# working.net
KiCad netlist of a schematic drawn in EAGLE
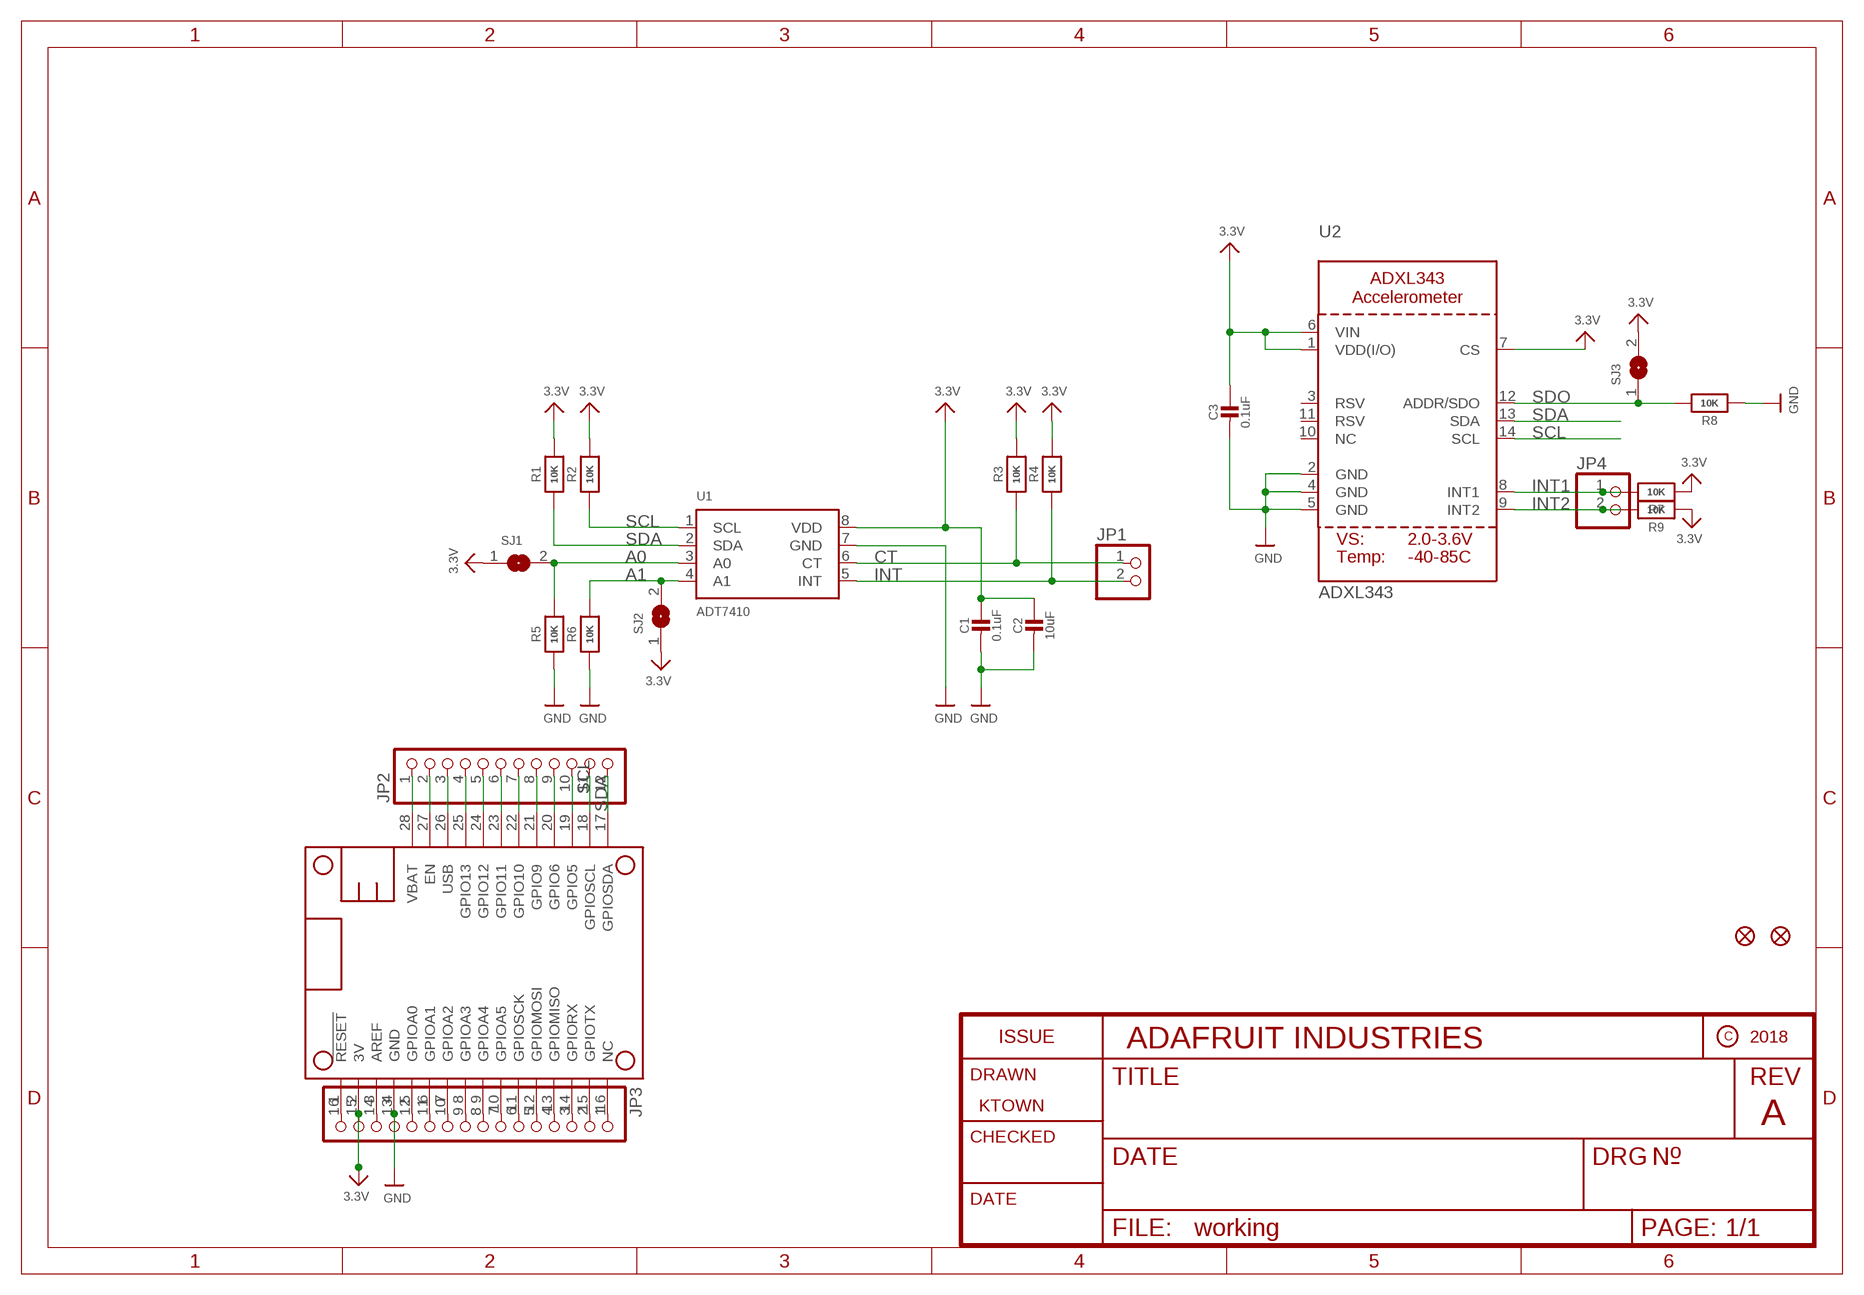
[diagram p0: schematic, sheet 1]

(export (version "E")
  (design (tool "Eeschema 10.0.6"))
  (components
    (comp (ref "C1")
      (value "0.1uF")
      (footprint "eagle-import:0603-NO")
      (libsource (lib "eagle-import") (part "CAP_CERAMIC0603_NO"))
    )
    (comp (ref "C2")
      (value "10uF")
      (footprint "eagle-import:0805-NO")
      (libsource (lib "eagle-import") (part "CAP_CERAMIC0805-NOOUTLINE"))
    )
    (comp (ref "C3")
      (value "0.1uF")
      (footprint "eagle-import:0603-NO")
      (libsource (lib "eagle-import") (part "CAP_CERAMIC0603_NO"))
    )
    (comp (ref "FID1")
      (value "FIDUCIAL_1MM")
      (footprint "eagle-import:FIDUCIAL_1MM")
      (libsource (lib "eagle-import") (part "FIDUCIAL_1MM"))
    )
    (comp (ref "FID2")
      (value "FIDUCIAL_1MM")
      (footprint "eagle-import:FIDUCIAL_1MM")
      (libsource (lib "eagle-import") (part "FIDUCIAL_1MM"))
    )
    (comp (ref "JP1")
      (value "HEADER-1X2ROUND")
      (footprint "eagle-import:1X02_ROUND")
      (libsource (lib "eagle-import") (part "HEADER-1X2ROUND"))
    )
    (comp (ref "JP2")
      (value "HEADER-1X1276MIL")
      (footprint "eagle-import:1X12_ROUND_76MIL")
      (libsource (lib "eagle-import") (part "HEADER-1X1276MIL"))
    )
    (comp (ref "JP3")
      (value "HEADER-1X16_76MIL")
      (footprint "eagle-import:1X16_ROUND_76MIL")
      (libsource (lib "eagle-import") (part "HEADER-1X16_76MIL"))
    )
    (comp (ref "JP4")
      (value "HEADER-1X2ROUND")
      (footprint "eagle-import:1X02_ROUND")
      (libsource (lib "eagle-import") (part "HEADER-1X2ROUND"))
    )
    (comp (ref "MS1")
      (value "FEATHERWING")
      (footprint "eagle-import:FEATHERWING")
      (libsource (lib "eagle-import") (part "FEATHERWING"))
    )
    (comp (ref "R1")
      (value "10K")
      (footprint "eagle-import:0603-NO")
      (libsource (lib "eagle-import") (part "RESISTOR_0603_NOOUT"))
    )
    (comp (ref "R2")
      (value "10K")
      (footprint "eagle-import:0603-NO")
      (libsource (lib "eagle-import") (part "RESISTOR_0603_NOOUT"))
    )
    (comp (ref "R3")
      (value "10K")
      (footprint "eagle-import:0603-NO")
      (libsource (lib "eagle-import") (part "RESISTOR_0603_NOOUT"))
    )
    (comp (ref "R4")
      (value "10K")
      (footprint "eagle-import:0603-NO")
      (libsource (lib "eagle-import") (part "RESISTOR_0603_NOOUT"))
    )
    (comp (ref "R5")
      (value "10K")
      (footprint "eagle-import:0603-NO")
      (libsource (lib "eagle-import") (part "RESISTOR_0603_NOOUT"))
    )
    (comp (ref "R6")
      (value "10K")
      (footprint "eagle-import:0603-NO")
      (libsource (lib "eagle-import") (part "RESISTOR_0603_NOOUT"))
    )
    (comp (ref "R7")
      (value "10K")
      (footprint "eagle-import:0603-NO")
      (libsource (lib "eagle-import") (part "RESISTOR_0603_NOOUT"))
    )
    (comp (ref "R8")
      (value "10K")
      (footprint "eagle-import:0603-NO")
      (libsource (lib "eagle-import") (part "RESISTOR_0603_NOOUT"))
    )
    (comp (ref "R9")
      (value "10K")
      (footprint "eagle-import:0603-NO")
      (libsource (lib "eagle-import") (part "RESISTOR_0603_NOOUT"))
    )
    (comp (ref "SJ1")
      (value "SOLDERJUMPER")
      (footprint "eagle-import:SOLDERJUMPER_ARROW_NOPASTE")
      (libsource (lib "eagle-import") (part "SOLDERJUMPER"))
    )
    (comp (ref "SJ2")
      (value "SOLDERJUMPER")
      (footprint "eagle-import:SOLDERJUMPER_ARROW_NOPASTE")
      (libsource (lib "eagle-import") (part "SOLDERJUMPER"))
    )
    (comp (ref "SJ3")
      (value "SOLDERJUMPER")
      (footprint "eagle-import:SOLDERJUMPER_ARROW_NOPASTE")
      (libsource (lib "eagle-import") (part "SOLDERJUMPER"))
    )
    (comp (ref "U1")
      (value "ADT7410")
      (footprint "eagle-import:SOIC8_150MIL")
      (libsource (lib "eagle-import") (part "TEMP_ADT7410"))
    )
    (comp (ref "U2")
      (value "ADXL343")
      (footprint "eagle-import:LGA14")
      (libsource (lib "eagle-import") (part "ACCEL_ADXL343"))
    )
  )
  (nets
    (net (code "1") (name "/A0") (class "Default")
      (node (ref "R5") (pin "2") (pinfunction "2_2") (pintype "passive"))
      (node (ref "SJ1") (pin "2") (pinfunction "2_2") (pintype "passive"))
      (node (ref "U1") (pin "3") (pinfunction "A0_3") (pintype "bidirectional"))
    )
    (net (code "2") (name "/A1") (class "Default")
      (node (ref "R6") (pin "2") (pinfunction "2_2") (pintype "passive"))
      (node (ref "SJ2") (pin "2") (pinfunction "2_2") (pintype "passive"))
      (node (ref "U1") (pin "4") (pinfunction "A1_4") (pintype "bidirectional"))
    )
    (net (code "3") (name "/CT") (class "Default")
      (node (ref "JP1") (pin "1") (pinfunction "1_1") (pintype "passive"))
      (node (ref "R3") (pin "1") (pinfunction "1_1") (pintype "passive"))
      (node (ref "U1") (pin "6") (pinfunction "CT_6") (pintype "bidirectional"))
    )
    (net (code "4") (name "/INT") (class "Default")
      (node (ref "JP1") (pin "2") (pinfunction "2_2") (pintype "passive"))
      (node (ref "R4") (pin "1") (pinfunction "1_1") (pintype "passive"))
      (node (ref "U1") (pin "5") (pinfunction "INT_5") (pintype "bidirectional"))
    )
    (net (code "5") (name "/INT1") (class "Default")
      (node (ref "JP4") (pin "1") (pinfunction "1_1") (pintype "passive"))
      (node (ref "R7") (pin "2") (pinfunction "2_2") (pintype "passive"))
      (node (ref "U2") (pin "8") (pinfunction "INT1_8") (pintype "bidirectional"))
    )
    (net (code "6") (name "/INT2") (class "Default")
      (node (ref "JP4") (pin "2") (pinfunction "2_2") (pintype "passive"))
      (node (ref "R9") (pin "2") (pinfunction "2_2") (pintype "passive"))
      (node (ref "U2") (pin "9") (pinfunction "INT2_9") (pintype "bidirectional"))
    )
    (net (code "7") (name "/SCL") (class "Default")
      (node (ref "JP2") (pin "11") (pinfunction "11_11") (pintype "passive"))
      (node (ref "MS1") (pin "18") (pinfunction "GPIOSCL_18") (pintype "bidirectional"))
      (node (ref "R2") (pin "1") (pinfunction "1_1") (pintype "passive"))
      (node (ref "U1") (pin "1") (pinfunction "SCL_1") (pintype "bidirectional"))
      (node (ref "U2") (pin "14") (pinfunction "SCL_14") (pintype "bidirectional"))
    )
    (net (code "8") (name "/SDA") (class "Default")
      (node (ref "JP2") (pin "12") (pinfunction "12_12") (pintype "passive"))
      (node (ref "MS1") (pin "17") (pinfunction "GPIOSDA_17") (pintype "bidirectional"))
      (node (ref "R1") (pin "1") (pinfunction "1_1") (pintype "passive"))
      (node (ref "U1") (pin "2") (pinfunction "SDA_2") (pintype "bidirectional"))
      (node (ref "U2") (pin "13") (pinfunction "SDA_13") (pintype "bidirectional"))
    )
    (net (code "9") (name "/SDO") (class "Default")
      (node (ref "R8") (pin "2") (pinfunction "2_2") (pintype "passive"))
      (node (ref "SJ3") (pin "1") (pinfunction "1_1") (pintype "passive"))
      (node (ref "U2") (pin "12") (pinfunction "ADDR/SDO_12") (pintype "bidirectional"))
    )
    (net (code "10") (name "3.3V") (class "Default")
      (node (ref "C1") (pin "1") (pinfunction "1_1") (pintype "passive"))
      (node (ref "C2") (pin "1") (pinfunction "1_1") (pintype "passive"))
      (node (ref "C3") (pin "1") (pinfunction "1_1") (pintype "passive"))
      (node (ref "JP3") (pin "15") (pinfunction "15_15") (pintype "passive"))
      (node (ref "MS1") (pin "2") (pinfunction "3V_2") (pintype "power_in"))
      (node (ref "R1") (pin "2") (pinfunction "2_2") (pintype "passive"))
      (node (ref "R2") (pin "2") (pinfunction "2_2") (pintype "passive"))
      (node (ref "R3") (pin "2") (pinfunction "2_2") (pintype "passive"))
      (node (ref "R4") (pin "2") (pinfunction "2_2") (pintype "passive"))
      (node (ref "R7") (pin "1") (pinfunction "1_1") (pintype "passive"))
      (node (ref "R9") (pin "1") (pinfunction "1_1") (pintype "passive"))
      (node (ref "SJ1") (pin "1") (pinfunction "1_1") (pintype "passive"))
      (node (ref "SJ2") (pin "1") (pinfunction "1_1") (pintype "passive"))
      (node (ref "SJ3") (pin "2") (pinfunction "2_2") (pintype "passive"))
      (node (ref "U1") (pin "8") (pinfunction "VDD_8") (pintype "power_in"))
      (node (ref "U2") (pin "1") (pinfunction "VDD(I/O)_1") (pintype "bidirectional"))
      (node (ref "U2") (pin "6") (pinfunction "VIN_6") (pintype "bidirectional"))
      (node (ref "U2") (pin "7") (pinfunction "CS_7") (pintype "bidirectional"))
    )
    (net (code "11") (name "GND") (class "Default")
      (node (ref "C1") (pin "2") (pinfunction "2_2") (pintype "passive"))
      (node (ref "C2") (pin "2") (pinfunction "2_2") (pintype "passive"))
      (node (ref "C3") (pin "2") (pinfunction "2_2") (pintype "passive"))
      (node (ref "JP3") (pin "13") (pinfunction "13_13") (pintype "passive"))
      (node (ref "MS1") (pin "4") (pinfunction "GND_4") (pintype "power_in"))
      (node (ref "R5") (pin "1") (pinfunction "1_1") (pintype "passive"))
      (node (ref "R6") (pin "1") (pinfunction "1_1") (pintype "passive"))
      (node (ref "R8") (pin "1") (pinfunction "1_1") (pintype "passive"))
      (node (ref "U1") (pin "7") (pinfunction "GND_7") (pintype "power_in"))
      (node (ref "U2") (pin "2") (pinfunction "GND_2") (pintype "bidirectional"))
      (node (ref "U2") (pin "4") (pinfunction "GND_4") (pintype "bidirectional"))
      (node (ref "U2") (pin "5") (pinfunction "GND_5") (pintype "bidirectional"))
    )
    (net (code "12") (name "Net-(MS1-AREF)") (class "Default")
      (node (ref "JP3") (pin "14") (pinfunction "14_14") (pintype "passive"))
      (node (ref "MS1") (pin "3") (pinfunction "AREF_3") (pintype "passive"))
    )
    (net (code "13") (name "Net-(MS1-EN)") (class "Default")
      (node (ref "JP2") (pin "2") (pinfunction "2_2") (pintype "passive"))
      (node (ref "MS1") (pin "27") (pinfunction "EN_27") (pintype "passive"))
    )
    (net (code "14") (name "Net-(MS1-GPIO5)") (class "Default")
      (node (ref "JP2") (pin "10") (pinfunction "10_10") (pintype "passive"))
      (node (ref "MS1") (pin "19") (pinfunction "GPIO5_19") (pintype "bidirectional"))
    )
    (net (code "15") (name "Net-(MS1-GPIO6)") (class "Default")
      (node (ref "JP2") (pin "9") (pinfunction "9_9") (pintype "passive"))
      (node (ref "MS1") (pin "20") (pinfunction "GPIO6_20") (pintype "bidirectional"))
    )
    (net (code "16") (name "Net-(MS1-GPIO9)") (class "Default")
      (node (ref "JP2") (pin "8") (pinfunction "8_8") (pintype "passive"))
      (node (ref "MS1") (pin "21") (pinfunction "GPIO9_21") (pintype "bidirectional"))
    )
    (net (code "17") (name "Net-(MS1-GPIO10)") (class "Default")
      (node (ref "JP2") (pin "7") (pinfunction "7_7") (pintype "passive"))
      (node (ref "MS1") (pin "22") (pinfunction "GPIO10_22") (pintype "bidirectional"))
    )
    (net (code "18") (name "Net-(MS1-GPIO11)") (class "Default")
      (node (ref "JP2") (pin "6") (pinfunction "6_6") (pintype "passive"))
      (node (ref "MS1") (pin "23") (pinfunction "GPIO11_23") (pintype "bidirectional"))
    )
    (net (code "19") (name "Net-(MS1-GPIO12)") (class "Default")
      (node (ref "JP2") (pin "5") (pinfunction "5_5") (pintype "passive"))
      (node (ref "MS1") (pin "24") (pinfunction "GPIO12_24") (pintype "bidirectional"))
    )
    (net (code "20") (name "Net-(MS1-GPIO13)") (class "Default")
      (node (ref "JP2") (pin "4") (pinfunction "4_4") (pintype "passive"))
      (node (ref "MS1") (pin "25") (pinfunction "GPIO13_25") (pintype "bidirectional"))
    )
    (net (code "21") (name "Net-(MS1-GPIOA0)") (class "Default")
      (node (ref "JP3") (pin "12") (pinfunction "12_12") (pintype "passive"))
      (node (ref "MS1") (pin "5") (pinfunction "GPIOA0_5") (pintype "bidirectional"))
    )
    (net (code "22") (name "Net-(MS1-GPIOA1)") (class "Default")
      (node (ref "JP3") (pin "11") (pinfunction "11_11") (pintype "passive"))
      (node (ref "MS1") (pin "6") (pinfunction "GPIOA1_6") (pintype "bidirectional"))
    )
    (net (code "23") (name "Net-(MS1-GPIOA2)") (class "Default")
      (node (ref "JP3") (pin "10") (pinfunction "10_10") (pintype "passive"))
      (node (ref "MS1") (pin "7") (pinfunction "GPIOA2_7") (pintype "bidirectional"))
    )
    (net (code "24") (name "Net-(MS1-GPIOA3)") (class "Default")
      (node (ref "JP3") (pin "9") (pinfunction "9_9") (pintype "passive"))
      (node (ref "MS1") (pin "8") (pinfunction "GPIOA3_8") (pintype "bidirectional"))
    )
    (net (code "25") (name "Net-(MS1-GPIOA4)") (class "Default")
      (node (ref "JP3") (pin "8") (pinfunction "8_8") (pintype "passive"))
      (node (ref "MS1") (pin "9") (pinfunction "GPIOA4_9") (pintype "bidirectional"))
    )
    (net (code "26") (name "Net-(MS1-GPIOA5)") (class "Default")
      (node (ref "JP3") (pin "7") (pinfunction "7_7") (pintype "passive"))
      (node (ref "MS1") (pin "10") (pinfunction "GPIOA5_10") (pintype "bidirectional"))
    )
    (net (code "27") (name "Net-(MS1-GPIOMISO)") (class "Default")
      (node (ref "JP3") (pin "4") (pinfunction "4_4") (pintype "passive"))
      (node (ref "MS1") (pin "13") (pinfunction "GPIOMISO_13") (pintype "bidirectional"))
    )
    (net (code "28") (name "Net-(MS1-GPIOMOSI)") (class "Default")
      (node (ref "JP3") (pin "5") (pinfunction "5_5") (pintype "passive"))
      (node (ref "MS1") (pin "12") (pinfunction "GPIOMOSI_12") (pintype "bidirectional"))
    )
    (net (code "29") (name "Net-(MS1-GPIORX)") (class "Default")
      (node (ref "JP3") (pin "3") (pinfunction "3_3") (pintype "passive"))
      (node (ref "MS1") (pin "14") (pinfunction "GPIORX_14") (pintype "bidirectional"))
    )
    (net (code "30") (name "Net-(MS1-GPIOSCK)") (class "Default")
      (node (ref "JP3") (pin "6") (pinfunction "6_6") (pintype "passive"))
      (node (ref "MS1") (pin "11") (pinfunction "GPIOSCK_11") (pintype "bidirectional"))
    )
    (net (code "31") (name "Net-(MS1-GPIOTX)") (class "Default")
      (node (ref "JP3") (pin "2") (pinfunction "2_2") (pintype "passive"))
      (node (ref "MS1") (pin "15") (pinfunction "GPIOTX_15") (pintype "bidirectional"))
    )
    (net (code "32") (name "Net-(MS1-NC)") (class "Default")
      (node (ref "JP3") (pin "1") (pinfunction "1_1") (pintype "passive"))
      (node (ref "MS1") (pin "16") (pinfunction "NC_16") (pintype "passive"))
    )
    (net (code "33") (name "Net-(MS1-USB)") (class "Default")
      (node (ref "JP2") (pin "3") (pinfunction "3_3") (pintype "passive"))
      (node (ref "MS1") (pin "26") (pinfunction "USB_26") (pintype "power_in"))
    )
    (net (code "34") (name "Net-(MS1-VBAT)") (class "Default")
      (node (ref "JP2") (pin "1") (pinfunction "1_1") (pintype "passive"))
      (node (ref "MS1") (pin "28") (pinfunction "VBAT_28") (pintype "power_in"))
    )
    (net (code "35") (name "Net-(MS1-~{RESET})") (class "Default")
      (node (ref "JP3") (pin "16") (pinfunction "16_16") (pintype "passive"))
      (node (ref "MS1") (pin "1") (pinfunction "~{RESET}_1") (pintype "input"))
    )
    (net (code "36") (name "unconnected-(U2-NC-Pad10)") (class "Default")
      (node (ref "U2") (pin "10") (pinfunction "NC_10") (pintype "bidirectional"))
    )
    (net (code "37") (name "unconnected-(U2-RSV-Pad3)") (class "Default")
      (node (ref "U2") (pin "3") (pinfunction "RSV_3") (pintype "bidirectional"))
    )
    (net (code "38") (name "unconnected-(U2-RSV-Pad11)") (class "Default")
      (node (ref "U2") (pin "11") (pinfunction "RSV_11") (pintype "bidirectional"))
    )
  )
)
